# 1Sheeld_Schematics_v1_0_0.net
KiCad netlist of a schematic drawn in EAGLE
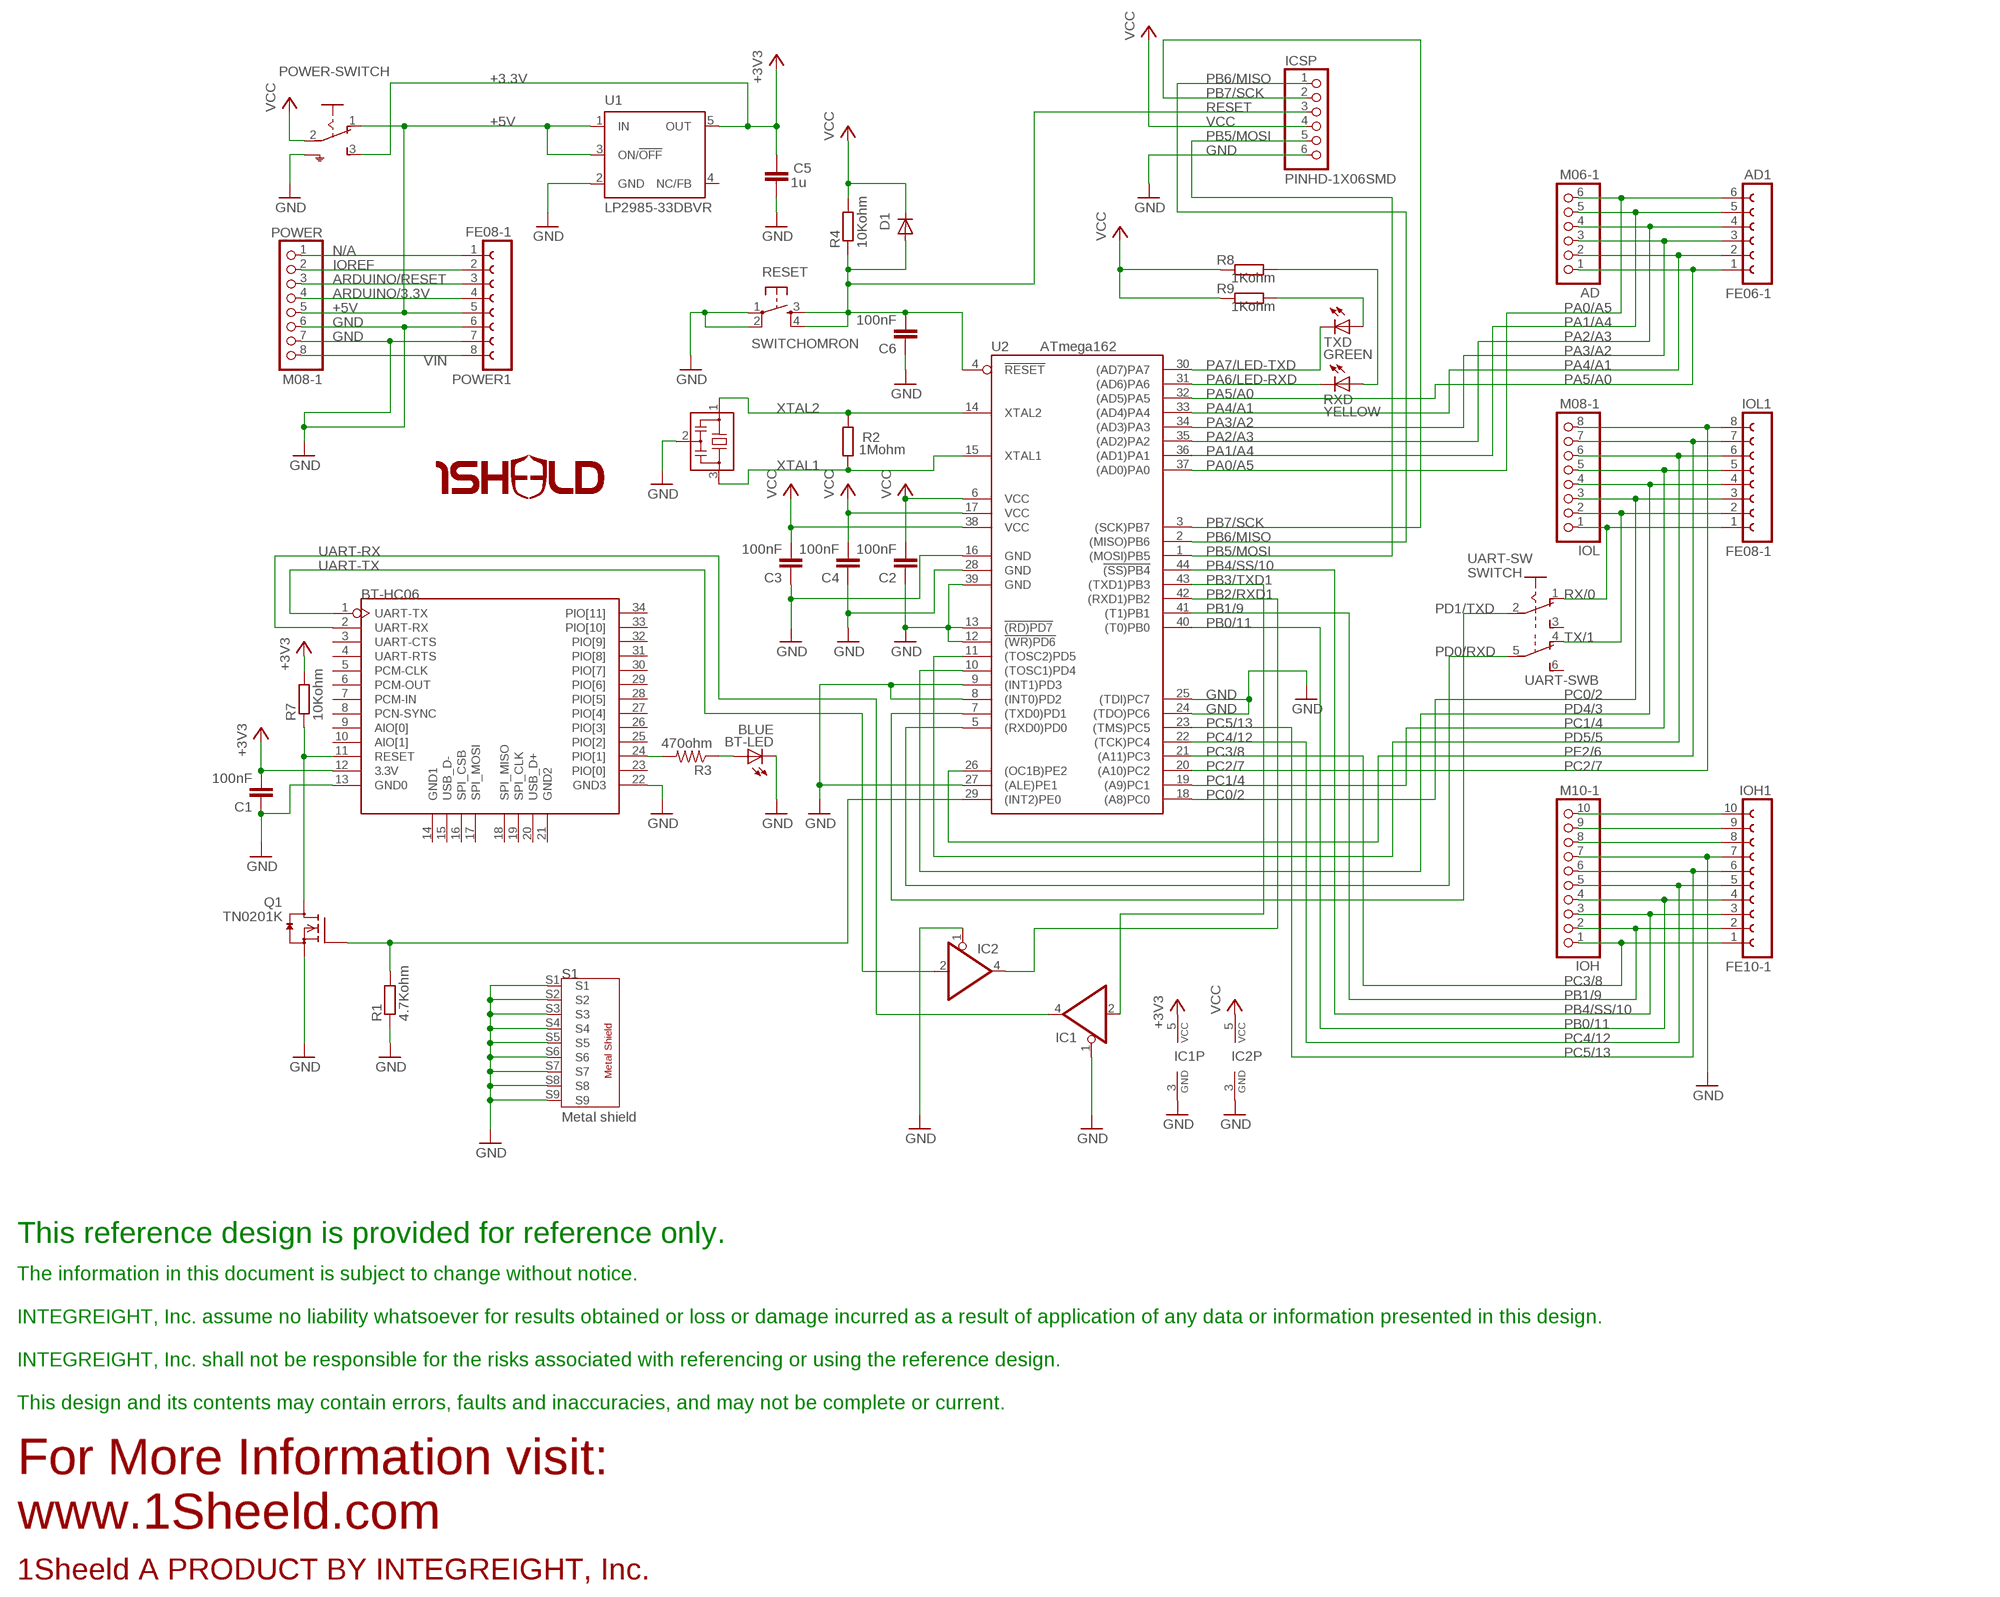
[diagram p0: schematic, sheet 1]

(export (version "E")
  (design (tool "Eeschema 10.0.6"))
  (components
    (comp (ref "AD")
      (value "M06-1")
      (footprint "eagle-import:1X06")
      (libsource (lib "eagle-import") (part "PINHD-1X6"))
    )
    (comp (ref "AD1")
      (value "FE06-1")
      (footprint "eagle-import:FE06")
      (libsource (lib "eagle-import") (part "FE06-1"))
    )
    (comp (ref "BT-HC06")
      (value "BLUETOOTH-SERIALSMD")
      (footprint "eagle-import:SERIAL_BLUETEETH")
      (libsource (lib "eagle-import") (part "BLUETOOTH-SERIALSMD"))
    )
    (comp (ref "BT-LED")
      (value "BLUE")
      (footprint "eagle-import:CHIP-LED0805")
      (libsource (lib "eagle-import") (part "LEDCHIP-LED0805"))
    )
    (comp (ref "C1")
      (value "100nF")
      (footprint "eagle-import:C0603-ROUND")
      (libsource (lib "eagle-import") (part "C-EU0603-RND"))
    )
    (comp (ref "C2")
      (value "100nF")
      (footprint "eagle-import:C0603-ROUND")
      (libsource (lib "eagle-import") (part "C-EU0603-RND"))
    )
    (comp (ref "C3")
      (value "100nF")
      (footprint "eagle-import:C0603-ROUND")
      (libsource (lib "eagle-import") (part "C-EU0603-RND"))
    )
    (comp (ref "C4")
      (value "100nF")
      (footprint "eagle-import:C0603-ROUND")
      (libsource (lib "eagle-import") (part "C-EU0603-RND"))
    )
    (comp (ref "C5")
      (value "1u")
      (footprint "eagle-import:C0603-ROUND")
      (libsource (lib "eagle-import") (part "C-EU0603-RND"))
    )
    (comp (ref "C6")
      (value "100nF")
      (footprint "eagle-import:C0603-ROUND")
      (libsource (lib "eagle-import") (part "C-EU0603-RND"))
    )
    (comp (ref "D1")
      (value "CD1206-S01575")
      (footprint "eagle-import:MINIMELF")
      (libsource (lib "eagle-import") (part "DIODE-MINIMELF"))
    )
    (comp (ref "IC1")
      (value "74LVC1G125DBV")
      (footprint "eagle-import:SOT23-5")
      (libsource (lib "eagle-import") (part "741G125DBVLVC"))
    )
    (comp (ref "IC2")
      (value "74LVC1G125DBV")
      (footprint "eagle-import:SOT23-5")
      (libsource (lib "eagle-import") (part "741G125DBVLVC"))
    )
    (comp (ref "ICSP")
      (value "PINHD-1X06SMD")
      (footprint "eagle-import:1X06_90SMD")
      (libsource (lib "eagle-import") (part "PINHD-1X06SMD"))
    )
    (comp (ref "IOH")
      (value "M10-1")
      (footprint "eagle-import:1X10")
      (libsource (lib "eagle-import") (part "PINHD-1X10_ARD"))
    )
    (comp (ref "IOH1")
      (value "FE10-1")
      (footprint "eagle-import:FE10")
      (libsource (lib "eagle-import") (part "FE10-1"))
    )
    (comp (ref "IOL")
      (value "M08-1")
      (footprint "eagle-import:1X08")
      (libsource (lib "eagle-import") (part "PINHD-1X8"))
    )
    (comp (ref "IOL1")
      (value "FE08-1")
      (footprint "eagle-import:FE08")
      (libsource (lib "eagle-import") (part "FE08-1"))
    )
    (comp (ref "POWER")
      (value "M08-1")
      (footprint "eagle-import:1X08")
      (libsource (lib "eagle-import") (part "PINHD-1X8"))
    )
    (comp (ref "POWER-SWITCH")
      (value "MULTICOMP - MSS3-V-T/R")
      (footprint "eagle-import:SWITCHMULTI")
      (fields (field (name "MANUFACTURER-PART") "MSS3-V-T/R"))
      (libsource (lib "eagle-import") (part "SWITCHMULTI"))
    )
    (comp (ref "POWER1")
      (value "FE08-1")
      (footprint "eagle-import:FE08")
      (libsource (lib "eagle-import") (part "FE08-1"))
    )
    (comp (ref "Q1")
      (value "TN0201K")
      (footprint "eagle-import:SOT23")
      (libsource (lib "eagle-import") (part "TN0201K"))
    )
    (comp (ref "R1")
      (value "4.7Kohm")
      (footprint "eagle-import:M0805")
      (libsource (lib "eagle-import") (part "rcl_R-EU_M0805"))
    )
    (comp (ref "R2")
      (value "1Mohm")
      (footprint "eagle-import:R0603-ROUND")
      (libsource (lib "eagle-import") (part "R-EU_R0603"))
    )
    (comp (ref "R3")
      (value "470ohm")
      (footprint "eagle-import:0402-RES")
      (libsource (lib "eagle-import") (part "RESISTOR0402-RES"))
    )
    (comp (ref "R4")
      (value "10Kohm")
      (footprint "eagle-import:M0805")
      (libsource (lib "eagle-import") (part "rcl_R-EU_M0805"))
    )
    (comp (ref "R7")
      (value "10Kohm")
      (footprint "eagle-import:M0805")
      (libsource (lib "eagle-import") (part "rcl_R-EU_M0805"))
    )
    (comp (ref "R8")
      (value "1Kohm")
      (footprint "eagle-import:R0603-ROUND")
      (libsource (lib "eagle-import") (part "R-EU_R0603"))
    )
    (comp (ref "R9")
      (value "1Kohm")
      (footprint "eagle-import:R0603-ROUND")
      (libsource (lib "eagle-import") (part "R-EU_R0603"))
    )
    (comp (ref "RESET")
      (value "SWITCHOMRON")
      (footprint "eagle-import:OMRONSWITCH")
      (fields (field (name "MANUFACTURER-PART") "B3SL-1022P "))
      (libsource (lib "eagle-import") (part "SWITCHOMRON"))
    )
    (comp (ref "RXD")
      (value "YELLOW")
      (footprint "eagle-import:CHIP-LED0805")
      (libsource (lib "eagle-import") (part "LEDCHIP-LED0805"))
    )
    (comp (ref "S1")
      (value "Metal shield")
      (footprint "eagle-import:BT_SHIELD")
      (libsource (lib "eagle-import") (part "EMI_SHIELD_BT"))
    )
    (comp (ref "TXD")
      (value "GREEN")
      (footprint "eagle-import:CHIP-LED0805")
      (libsource (lib "eagle-import") (part "LEDCHIP-LED0805"))
    )
    (comp (ref "U1")
      (value "LP2985-33DBVR")
      (footprint "eagle-import:SOT23-DBV")
      (libsource (lib "eagle-import") (part "LP2985-XXDBVR33"))
    )
    (comp (ref "U2")
      (value "ATmega162")
      (footprint "eagle-import:TQFP44")
      (libsource (lib "eagle-import") (part "ATMEGA162"))
    )
    (comp (ref "UART-SW")
      (value "SWITCH")
      (footprint "eagle-import:SWITCH")
      (libsource (lib "eagle-import") (part "SWITCH"))
    )
    (comp (ref "Y1")
      (value "CSTCR7M37G53-R0 7.37MHZ")
      (footprint "eagle-import:CSTCR6M")
      (libsource (lib "eagle-import") (part "CSTCR7M37G53-R0"))
    )
  )
  (nets
    (net (code "1") (name "+3V3") (class "Default")
      (node (ref "BT-HC06") (pin "12") (pinfunction "3.3V_12") (pintype "bidirectional"))
      (node (ref "C1") (pin "2") (pinfunction "2_2") (pintype "passive"))
      (node (ref "C5") (pin "2") (pinfunction "2_2") (pintype "passive"))
      (node (ref "IC1") (pin "5") (pinfunction "VCC_5") (pintype "power_in"))
      (node (ref "POWER-SWITCH") (pin "3") (pinfunction "S_3") (pintype "passive"))
      (node (ref "R7") (pin "2") (pinfunction "2_2") (pintype "passive"))
      (node (ref "U1") (pin "5") (pinfunction "OUT_5") (pintype "passive"))
    )
    (net (code "2") (name "/+5V") (class "Default")
      (node (ref "POWER") (pin "5") (pinfunction "5_5") (pintype "passive"))
      (node (ref "POWER-SWITCH") (pin "1") (pinfunction "O_1") (pintype "passive"))
      (node (ref "POWER1") (pin "5") (pinfunction "5_5") (pintype "passive"))
      (node (ref "U1") (pin "1") (pinfunction "IN_1") (pintype "input"))
      (node (ref "U1") (pin "3") (pinfunction "ON/~{OFF}_3") (pintype "input"))
    )
    (net (code "3") (name "/ARDUINO{slash}3.3V") (class "Default")
      (node (ref "POWER") (pin "4") (pinfunction "4_4") (pintype "passive"))
      (node (ref "POWER1") (pin "4") (pinfunction "4_4") (pintype "passive"))
    )
    (net (code "4") (name "/ARDUINO{slash}RESET") (class "Default")
      (node (ref "POWER") (pin "3") (pinfunction "3_3") (pintype "passive"))
      (node (ref "POWER1") (pin "3") (pinfunction "3_3") (pintype "passive"))
    )
    (net (code "5") (name "/IOREF") (class "Default")
      (node (ref "POWER") (pin "2") (pinfunction "2_2") (pintype "passive"))
      (node (ref "POWER1") (pin "2") (pinfunction "2_2") (pintype "passive"))
    )
    (net (code "6") (name "/N{slash}A") (class "Default")
      (node (ref "POWER") (pin "1") (pinfunction "1_1") (pintype "passive"))
      (node (ref "POWER1") (pin "1") (pinfunction "1_1") (pintype "passive"))
    )
    (net (code "7") (name "/PA0{slash}A5") (class "Default")
      (node (ref "AD") (pin "6") (pinfunction "6_6") (pintype "passive"))
      (node (ref "AD1") (pin "6") (pinfunction "6_6") (pintype "passive"))
      (node (ref "U2") (pin "37") (pinfunction "(AD0)PA0_37") (pintype "bidirectional"))
    )
    (net (code "8") (name "/PA1{slash}A4") (class "Default")
      (node (ref "AD") (pin "5") (pinfunction "5_5") (pintype "passive"))
      (node (ref "AD1") (pin "5") (pinfunction "5_5") (pintype "passive"))
      (node (ref "U2") (pin "36") (pinfunction "(AD1)PA1_36") (pintype "bidirectional"))
    )
    (net (code "9") (name "/PA2{slash}A3") (class "Default")
      (node (ref "AD") (pin "4") (pinfunction "4_4") (pintype "passive"))
      (node (ref "AD1") (pin "4") (pinfunction "4_4") (pintype "passive"))
      (node (ref "U2") (pin "35") (pinfunction "(AD2)PA2_35") (pintype "bidirectional"))
    )
    (net (code "10") (name "/PA3{slash}A2") (class "Default")
      (node (ref "AD") (pin "3") (pinfunction "3_3") (pintype "passive"))
      (node (ref "AD1") (pin "3") (pinfunction "3_3") (pintype "passive"))
      (node (ref "U2") (pin "34") (pinfunction "(AD3)PA3_34") (pintype "bidirectional"))
    )
    (net (code "11") (name "/PA4{slash}A1") (class "Default")
      (node (ref "AD") (pin "2") (pinfunction "2_2") (pintype "passive"))
      (node (ref "AD1") (pin "2") (pinfunction "2_2") (pintype "passive"))
      (node (ref "U2") (pin "33") (pinfunction "(AD4)PA4_33") (pintype "bidirectional"))
    )
    (net (code "12") (name "/PA5{slash}A0") (class "Default")
      (node (ref "AD") (pin "1") (pinfunction "1_1") (pintype "passive"))
      (node (ref "AD1") (pin "1") (pinfunction "1_1") (pintype "passive"))
      (node (ref "U2") (pin "32") (pinfunction "(AD5)PA5_32") (pintype "bidirectional"))
    )
    (net (code "13") (name "/PA6{slash}LED-RXD") (class "Default")
      (node (ref "RXD") (pin "C") (pinfunction "C_C") (pintype "passive"))
      (node (ref "U2") (pin "31") (pinfunction "(AD6)PA6_31") (pintype "bidirectional"))
    )
    (net (code "14") (name "/PA7{slash}LED-TXD") (class "Default")
      (node (ref "TXD") (pin "C") (pinfunction "C_C") (pintype "passive"))
      (node (ref "U2") (pin "30") (pinfunction "(AD7)PA7_30") (pintype "bidirectional"))
    )
    (net (code "15") (name "/PB0{slash}11") (class "Default")
      (node (ref "IOH") (pin "4") (pinfunction "4_4") (pintype "passive"))
      (node (ref "IOH1") (pin "4") (pinfunction "4_4") (pintype "passive"))
      (node (ref "U2") (pin "40") (pinfunction "(T0)PB0_40") (pintype "bidirectional"))
    )
    (net (code "16") (name "/PB1{slash}9") (class "Default")
      (node (ref "IOH") (pin "2") (pinfunction "2_2") (pintype "passive"))
      (node (ref "IOH1") (pin "2") (pinfunction "2_2") (pintype "passive"))
      (node (ref "U2") (pin "41") (pinfunction "(T1)PB1_41") (pintype "bidirectional"))
    )
    (net (code "17") (name "/PB2{slash}RXD1") (class "Default")
      (node (ref "IC2") (pin "4") (pinfunction "O_4") (pintype "tri_state"))
      (node (ref "U2") (pin "42") (pinfunction "(RXD1)PB2_42") (pintype "bidirectional"))
    )
    (net (code "18") (name "/PB3{slash}TXD1") (class "Default")
      (node (ref "IC1") (pin "2") (pinfunction "I_2") (pintype "input"))
      (node (ref "U2") (pin "43") (pinfunction "(TXD1)PB3_43") (pintype "bidirectional"))
    )
    (net (code "19") (name "/PB4{slash}SS{slash}10") (class "Default")
      (node (ref "IOH") (pin "3") (pinfunction "3_3") (pintype "passive"))
      (node (ref "IOH1") (pin "3") (pinfunction "3_3") (pintype "passive"))
      (node (ref "U2") (pin "44") (pinfunction "~{(SS})PB4_44") (pintype "bidirectional"))
    )
    (net (code "20") (name "/PB5{slash}MOSI") (class "Default")
      (node (ref "ICSP") (pin "5") (pinfunction "5_5") (pintype "passive"))
      (node (ref "U2") (pin "1") (pinfunction "(MOSI)PB5_1") (pintype "bidirectional"))
    )
    (net (code "21") (name "/PB6{slash}MISO") (class "Default")
      (node (ref "ICSP") (pin "1") (pinfunction "1_1") (pintype "passive"))
      (node (ref "U2") (pin "2") (pinfunction "(MISO)PB6_2") (pintype "bidirectional"))
    )
    (net (code "22") (name "/PB7{slash}SCK") (class "Default")
      (node (ref "ICSP") (pin "2") (pinfunction "2_2") (pintype "passive"))
      (node (ref "U2") (pin "3") (pinfunction "(SCK)PB7_3") (pintype "bidirectional"))
    )
    (net (code "23") (name "/PC0{slash}2") (class "Default")
      (node (ref "IOL") (pin "3") (pinfunction "3_3") (pintype "passive"))
      (node (ref "IOL1") (pin "3") (pinfunction "3_3") (pintype "passive"))
      (node (ref "U2") (pin "18") (pinfunction "(A8)PC0_18") (pintype "bidirectional"))
    )
    (net (code "24") (name "/PC1{slash}4") (class "Default")
      (node (ref "IOL") (pin "5") (pinfunction "5_5") (pintype "passive"))
      (node (ref "IOL1") (pin "5") (pinfunction "5_5") (pintype "passive"))
      (node (ref "U2") (pin "19") (pinfunction "(A9)PC1_19") (pintype "bidirectional"))
    )
    (net (code "25") (name "/PC2{slash}7") (class "Default")
      (node (ref "IOL") (pin "8") (pinfunction "8_8") (pintype "passive"))
      (node (ref "IOL1") (pin "8") (pinfunction "8_8") (pintype "passive"))
      (node (ref "U2") (pin "20") (pinfunction "(A10)PC2_20") (pintype "bidirectional"))
    )
    (net (code "26") (name "/PC3{slash}8") (class "Default")
      (node (ref "IOH") (pin "1") (pinfunction "1_1") (pintype "passive"))
      (node (ref "IOH1") (pin "1") (pinfunction "1_1") (pintype "passive"))
      (node (ref "U2") (pin "21") (pinfunction "(A11)PC3_21") (pintype "bidirectional"))
    )
    (net (code "27") (name "/PC4{slash}12") (class "Default")
      (node (ref "IOH") (pin "5") (pinfunction "5_5") (pintype "passive"))
      (node (ref "IOH1") (pin "5") (pinfunction "5_5") (pintype "passive"))
      (node (ref "U2") (pin "22") (pinfunction "(TCK)PC4_22") (pintype "bidirectional"))
    )
    (net (code "28") (name "/PC5{slash}13") (class "Default")
      (node (ref "IOH") (pin "6") (pinfunction "6_6") (pintype "passive"))
      (node (ref "IOH1") (pin "6") (pinfunction "6_6") (pintype "passive"))
      (node (ref "U2") (pin "23") (pinfunction "(TMS)PC5_23") (pintype "bidirectional"))
    )
    (net (code "29") (name "/PD0{slash}RXD") (class "Default")
      (node (ref "U2") (pin "5") (pinfunction "(RXD0)PD0_5") (pintype "bidirectional"))
      (node (ref "UART-SW") (pin "5") (pinfunction "P_5") (pintype "passive"))
    )
    (net (code "30") (name "/PD1{slash}TXD") (class "Default")
      (node (ref "U2") (pin "7") (pinfunction "(TXD0)PD1_7") (pintype "bidirectional"))
      (node (ref "UART-SW") (pin "2") (pinfunction "P_2") (pintype "passive"))
    )
    (net (code "31") (name "/PD4{slash}3") (class "Default")
      (node (ref "IOL") (pin "4") (pinfunction "4_4") (pintype "passive"))
      (node (ref "IOL1") (pin "4") (pinfunction "4_4") (pintype "passive"))
      (node (ref "U2") (pin "10") (pinfunction "(TOSC1)PD4_10") (pintype "bidirectional"))
    )
    (net (code "32") (name "/PD5{slash}5") (class "Default")
      (node (ref "IOL") (pin "6") (pinfunction "6_6") (pintype "passive"))
      (node (ref "IOL1") (pin "6") (pinfunction "6_6") (pintype "passive"))
      (node (ref "U2") (pin "11") (pinfunction "(TOSC2)PD5_11") (pintype "bidirectional"))
    )
    (net (code "33") (name "/PE2{slash}6") (class "Default")
      (node (ref "IOL") (pin "7") (pinfunction "7_7") (pintype "passive"))
      (node (ref "IOL1") (pin "7") (pinfunction "7_7") (pintype "passive"))
      (node (ref "U2") (pin "26") (pinfunction "(OC1B)PE2_26") (pintype "bidirectional"))
    )
    (net (code "34") (name "/RESET") (class "Default")
      (node (ref "C6") (pin "2") (pinfunction "2_2") (pintype "passive"))
      (node (ref "D1") (pin "A") (pinfunction "A_A") (pintype "passive"))
      (node (ref "ICSP") (pin "3") (pinfunction "3_3") (pintype "passive"))
      (node (ref "R4") (pin "1") (pinfunction "1_1") (pintype "passive"))
      (node (ref "RESET") (pin "3") (pinfunction "S_3") (pintype "passive"))
      (node (ref "RESET") (pin "4") (pinfunction "S1_4") (pintype "passive"))
      (node (ref "U2") (pin "4") (pinfunction "~{RESET}_4") (pintype "input"))
    )
    (net (code "35") (name "/RX{slash}0") (class "Default")
      (node (ref "IOL") (pin "1") (pinfunction "1_1") (pintype "passive"))
      (node (ref "IOL1") (pin "1") (pinfunction "1_1") (pintype "passive"))
      (node (ref "UART-SW") (pin "1") (pinfunction "O_1") (pintype "passive"))
    )
    (net (code "36") (name "/TX{slash}1") (class "Default")
      (node (ref "IOL") (pin "2") (pinfunction "2_2") (pintype "passive"))
      (node (ref "IOL1") (pin "2") (pinfunction "2_2") (pintype "passive"))
      (node (ref "UART-SW") (pin "4") (pinfunction "O_4") (pintype "passive"))
    )
    (net (code "37") (name "/UART-RX") (class "Default")
      (node (ref "BT-HC06") (pin "2") (pinfunction "UART-RX_2") (pintype "bidirectional"))
      (node (ref "IC1") (pin "4") (pinfunction "O_4") (pintype "tri_state"))
    )
    (net (code "38") (name "/UART-TX") (class "Default")
      (node (ref "BT-HC06") (pin "1") (pinfunction "UART-TX_1") (pintype "bidirectional"))
      (node (ref "IC2") (pin "2") (pinfunction "I_2") (pintype "input"))
    )
    (net (code "39") (name "/VIN") (class "Default")
      (node (ref "POWER") (pin "8") (pinfunction "8_8") (pintype "passive"))
      (node (ref "POWER1") (pin "8") (pinfunction "8_8") (pintype "passive"))
    )
    (net (code "40") (name "/XTAL1") (class "Default")
      (node (ref "R2") (pin "1") (pinfunction "1_1") (pintype "passive"))
      (node (ref "U2") (pin "15") (pinfunction "XTAL1_15") (pintype "input"))
      (node (ref "Y1") (pin "3") (pinfunction "3_3") (pintype "passive"))
    )
    (net (code "41") (name "/XTAL2") (class "Default")
      (node (ref "R2") (pin "2") (pinfunction "2_2") (pintype "passive"))
      (node (ref "U2") (pin "14") (pinfunction "XTAL2_14") (pintype "input"))
      (node (ref "Y1") (pin "1") (pinfunction "1_1") (pintype "passive"))
    )
    (net (code "42") (name "GND") (class "Default")
      (node (ref "BT-HC06") (pin "13") (pinfunction "GND0_13") (pintype "bidirectional"))
      (node (ref "BT-HC06") (pin "22") (pinfunction "GND3_22") (pintype "bidirectional"))
      (node (ref "BT-LED") (pin "C") (pinfunction "C_C") (pintype "passive"))
      (node (ref "C1") (pin "1") (pinfunction "1_1") (pintype "passive"))
      (node (ref "C2") (pin "1") (pinfunction "1_1") (pintype "passive"))
      (node (ref "C3") (pin "1") (pinfunction "1_1") (pintype "passive"))
      (node (ref "C4") (pin "1") (pinfunction "1_1") (pintype "passive"))
      (node (ref "C5") (pin "1") (pinfunction "1_1") (pintype "passive"))
      (node (ref "C6") (pin "1") (pinfunction "1_1") (pintype "passive"))
      (node (ref "IC1") (pin "1") (pinfunction "OE_1") (pintype "input"))
      (node (ref "IC1") (pin "3") (pinfunction "GND_3") (pintype "power_in"))
      (node (ref "IC2") (pin "1") (pinfunction "OE_1") (pintype "input"))
      (node (ref "IC2") (pin "3") (pinfunction "GND_3") (pintype "power_in"))
      (node (ref "ICSP") (pin "6") (pinfunction "6_6") (pintype "passive"))
      (node (ref "IOH") (pin "7") (pinfunction "7_7") (pintype "passive"))
      (node (ref "IOH1") (pin "7") (pinfunction "7_7") (pintype "passive"))
      (node (ref "POWER") (pin "6") (pinfunction "6_6") (pintype "passive"))
      (node (ref "POWER") (pin "7") (pinfunction "7_7") (pintype "passive"))
      (node (ref "POWER-SWITCH") (pin "P$4") (pinfunction "SH_P$4") (pintype "passive"))
      (node (ref "POWER-SWITCH") (pin "P$5") (pinfunction "SH_P$5") (pintype "passive"))
      (node (ref "POWER-SWITCH") (pin "P$6") (pinfunction "SH_P$6") (pintype "passive"))
      (node (ref "POWER-SWITCH") (pin "P$7") (pinfunction "SH_P$7") (pintype "passive"))
      (node (ref "POWER1") (pin "6") (pinfunction "6_6") (pintype "passive"))
      (node (ref "POWER1") (pin "7") (pinfunction "7_7") (pintype "passive"))
      (node (ref "Q1") (pin "2") (pinfunction "S_2") (pintype "passive"))
      (node (ref "R1") (pin "1") (pinfunction "1_1") (pintype "passive"))
      (node (ref "RESET") (pin "1") (pinfunction "P_1") (pintype "passive"))
      (node (ref "RESET") (pin "2") (pinfunction "P1_2") (pintype "passive"))
      (node (ref "S1") (pin "S1") (pinfunction "S1_S1") (pintype "bidirectional"))
      (node (ref "S1") (pin "S2") (pinfunction "S2_S2") (pintype "bidirectional"))
      (node (ref "S1") (pin "S3") (pinfunction "S3_S3") (pintype "bidirectional"))
      (node (ref "S1") (pin "S4") (pinfunction "S4_S4") (pintype "bidirectional"))
      (node (ref "S1") (pin "S5") (pinfunction "S5_S5") (pintype "bidirectional"))
      (node (ref "S1") (pin "S6") (pinfunction "S6_S6") (pintype "bidirectional"))
      (node (ref "S1") (pin "S7") (pinfunction "S7_S7") (pintype "bidirectional"))
      (node (ref "S1") (pin "S8") (pinfunction "S8_S8") (pintype "bidirectional"))
      (node (ref "S1") (pin "S9") (pinfunction "S9_S9") (pintype "bidirectional"))
      (node (ref "U1") (pin "2") (pinfunction "GND_2") (pintype "power_in"))
      (node (ref "U2") (pin "12") (pinfunction "~{(WR})PD6_12") (pintype "bidirectional"))
      (node (ref "U2") (pin "13") (pinfunction "~{(RD})PD7_13") (pintype "bidirectional"))
      (node (ref "U2") (pin "16") (pinfunction "GND_16") (pintype "power_in"))
      (node (ref "U2") (pin "24") (pinfunction "(TDO)PC6_24") (pintype "bidirectional"))
      (node (ref "U2") (pin "25") (pinfunction "(TDI)PC7_25") (pintype "bidirectional"))
      (node (ref "U2") (pin "27") (pinfunction "(ALE)PE1_27") (pintype "bidirectional"))
      (node (ref "U2") (pin "28") (pinfunction "GND_28") (pintype "power_in"))
      (node (ref "U2") (pin "39") (pinfunction "GND_39") (pintype "power_in"))
      (node (ref "U2") (pin "8") (pinfunction "(INT0)PD2_8") (pintype "bidirectional"))
      (node (ref "U2") (pin "9") (pinfunction "(INT1)PD3_9") (pintype "bidirectional"))
      (node (ref "Y1") (pin "2") (pinfunction "2_2") (pintype "passive"))
    )
    (net (code "43") (name "Net-(BT-HC06-PIO[1])") (class "Default")
      (node (ref "BT-HC06") (pin "24") (pinfunction "PIO[1]_24") (pintype "bidirectional"))
      (node (ref "R3") (pin "2") (pinfunction "2_2") (pintype "passive"))
    )
    (net (code "44") (name "Net-(BT-HC06-RESET)") (class "Default")
      (node (ref "BT-HC06") (pin "11") (pinfunction "RESET_11") (pintype "bidirectional"))
      (node (ref "Q1") (pin "3") (pinfunction "D_3") (pintype "passive"))
      (node (ref "R7") (pin "1") (pinfunction "1_1") (pintype "passive"))
    )
    (net (code "45") (name "Net-(BT-LED-PadA)") (class "Default")
      (node (ref "BT-LED") (pin "A") (pinfunction "A_A") (pintype "passive"))
      (node (ref "R3") (pin "1") (pinfunction "1_1") (pintype "passive"))
    )
    (net (code "46") (name "Net-(IOH-Pad8)") (class "Default")
      (node (ref "IOH") (pin "8") (pinfunction "8_8") (pintype "passive"))
      (node (ref "IOH1") (pin "8") (pinfunction "8_8") (pintype "passive"))
    )
    (net (code "47") (name "Net-(IOH-Pad9)") (class "Default")
      (node (ref "IOH") (pin "9") (pinfunction "9_9") (pintype "passive"))
      (node (ref "IOH1") (pin "9") (pinfunction "9_9") (pintype "passive"))
    )
    (net (code "48") (name "Net-(IOH-Pad10)") (class "Default")
      (node (ref "IOH") (pin "10") (pinfunction "10_10") (pintype "passive"))
      (node (ref "IOH1") (pin "10") (pinfunction "10_10") (pintype "passive"))
    )
    (net (code "49") (name "Net-(Q1-G)") (class "Default")
      (node (ref "Q1") (pin "1") (pinfunction "G_1") (pintype "passive"))
      (node (ref "R1") (pin "2") (pinfunction "2_2") (pintype "passive"))
      (node (ref "U2") (pin "29") (pinfunction "(INT2)PE0_29") (pintype "bidirectional"))
    )
    (net (code "50") (name "Net-(R8-Pad1)") (class "Default")
      (node (ref "R8") (pin "1") (pinfunction "1_1") (pintype "passive"))
      (node (ref "RXD") (pin "A") (pinfunction "A_A") (pintype "passive"))
    )
    (net (code "51") (name "Net-(R9-Pad1)") (class "Default")
      (node (ref "R9") (pin "1") (pinfunction "1_1") (pintype "passive"))
      (node (ref "TXD") (pin "A") (pinfunction "A_A") (pintype "passive"))
    )
    (net (code "52") (name "VCC") (class "Default")
      (node (ref "C2") (pin "2") (pinfunction "2_2") (pintype "passive"))
      (node (ref "C3") (pin "2") (pinfunction "2_2") (pintype "passive"))
      (node (ref "C4") (pin "2") (pinfunction "2_2") (pintype "passive"))
      (node (ref "D1") (pin "C") (pinfunction "C_C") (pintype "passive"))
      (node (ref "IC2") (pin "5") (pinfunction "VCC_5") (pintype "power_in"))
      (node (ref "ICSP") (pin "4") (pinfunction "4_4") (pintype "passive"))
      (node (ref "POWER-SWITCH") (pin "2") (pinfunction "P_2") (pintype "passive"))
      (node (ref "R4") (pin "2") (pinfunction "2_2") (pintype "passive"))
      (node (ref "R8") (pin "2") (pinfunction "2_2") (pintype "passive"))
      (node (ref "R9") (pin "2") (pinfunction "2_2") (pintype "passive"))
      (node (ref "U2") (pin "17") (pinfunction "VCC_17") (pintype "power_in"))
      (node (ref "U2") (pin "38") (pinfunction "VCC_38") (pintype "power_in"))
      (node (ref "U2") (pin "6") (pinfunction "VCC_6") (pintype "power_in"))
    )
    (net (code "53") (name "unconnected-(BT-HC06-AIO[0]-Pad9)") (class "Default")
      (node (ref "BT-HC06") (pin "9") (pinfunction "AIO[0]_9") (pintype "bidirectional"))
    )
    (net (code "54") (name "unconnected-(BT-HC06-AIO[1]-Pad10)") (class "Default")
      (node (ref "BT-HC06") (pin "10") (pinfunction "AIO[1]_10") (pintype "bidirectional"))
    )
    (net (code "55") (name "unconnected-(BT-HC06-GND1-Pad14)") (class "Default")
      (node (ref "BT-HC06") (pin "14") (pinfunction "GND1_14") (pintype "bidirectional"))
    )
    (net (code "56") (name "unconnected-(BT-HC06-GND2-Pad21)") (class "Default")
      (node (ref "BT-HC06") (pin "21") (pinfunction "GND2_21") (pintype "bidirectional"))
    )
    (net (code "57") (name "unconnected-(BT-HC06-PCM-CLK-Pad5)") (class "Default")
      (node (ref "BT-HC06") (pin "5") (pinfunction "PCM-CLK_5") (pintype "bidirectional"))
    )
    (net (code "58") (name "unconnected-(BT-HC06-PCM-IN-Pad7)") (class "Default")
      (node (ref "BT-HC06") (pin "7") (pinfunction "PCM-IN_7") (pintype "bidirectional"))
    )
    (net (code "59") (name "unconnected-(BT-HC06-PCM-OUT-Pad6)") (class "Default")
      (node (ref "BT-HC06") (pin "6") (pinfunction "PCM-OUT_6") (pintype "bidirectional"))
    )
    (net (code "60") (name "unconnected-(BT-HC06-PCN-SYNC-Pad8)") (class "Default")
      (node (ref "BT-HC06") (pin "8") (pinfunction "PCN-SYNC_8") (pintype "bidirectional"))
    )
    (net (code "61") (name "unconnected-(BT-HC06-PIO[0]-Pad23)") (class "Default")
      (node (ref "BT-HC06") (pin "23") (pinfunction "PIO[0]_23") (pintype "bidirectional"))
    )
    (net (code "62") (name "unconnected-(BT-HC06-PIO[2]-Pad25)") (class "Default")
      (node (ref "BT-HC06") (pin "25") (pinfunction "PIO[2]_25") (pintype "bidirectional"))
    )
    (net (code "63") (name "unconnected-(BT-HC06-PIO[3]-Pad26)") (class "Default")
      (node (ref "BT-HC06") (pin "26") (pinfunction "PIO[3]_26") (pintype "bidirectional"))
    )
    (net (code "64") (name "unconnected-(BT-HC06-PIO[4]-Pad27)") (class "Default")
      (node (ref "BT-HC06") (pin "27") (pinfunction "PIO[4]_27") (pintype "bidirectional"))
    )
    (net (code "65") (name "unconnected-(BT-HC06-PIO[5]-Pad28)") (class "Default")
      (node (ref "BT-HC06") (pin "28") (pinfunction "PIO[5]_28") (pintype "bidirectional"))
    )
    (net (code "66") (name "unconnected-(BT-HC06-PIO[6]-Pad29)") (class "Default")
      (node (ref "BT-HC06") (pin "29") (pinfunction "PIO[6]_29") (pintype "bidirectional"))
    )
    (net (code "67") (name "unconnected-(BT-HC06-PIO[7]-Pad30)") (class "Default")
      (node (ref "BT-HC06") (pin "30") (pinfunction "PIO[7]_30") (pintype "bidirectional"))
    )
    (net (code "68") (name "unconnected-(BT-HC06-PIO[8]-Pad31)") (class "Default")
      (node (ref "BT-HC06") (pin "31") (pinfunction "PIO[8]_31") (pintype "bidirectional"))
    )
    (net (code "69") (name "unconnected-(BT-HC06-PIO[9]-Pad32)") (class "Default")
      (node (ref "BT-HC06") (pin "32") (pinfunction "PIO[9]_32") (pintype "bidirectional"))
    )
    (net (code "70") (name "unconnected-(BT-HC06-PIO[10]-Pad33)") (class "Default")
      (node (ref "BT-HC06") (pin "33") (pinfunction "PIO[10]_33") (pintype "bidirectional"))
    )
    (net (code "71") (name "unconnected-(BT-HC06-PIO[11]-Pad34)") (class "Default")
      (node (ref "BT-HC06") (pin "34") (pinfunction "PIO[11]_34") (pintype "bidirectional"))
    )
    (net (code "72") (name "unconnected-(BT-HC06-SPI_CLK-Pad19)") (class "Default")
      (node (ref "BT-HC06") (pin "19") (pinfunction "SPI_CLK_19") (pintype "bidirectional"))
    )
    (net (code "73") (name "unconnected-(BT-HC06-SPI_CSB-Pad16)") (class "Default")
      (node (ref "BT-HC06") (pin "16") (pinfunction "SPI_CSB_16") (pintype "bidirectional"))
    )
    (net (code "74") (name "unconnected-(BT-HC06-SPI_MISO-Pad18)") (class "Default")
      (node (ref "BT-HC06") (pin "18") (pinfunction "SPI_MISO_18") (pintype "bidirectional"))
    )
    (net (code "75") (name "unconnected-(BT-HC06-SPI_MOSI-Pad17)") (class "Default")
      (node (ref "BT-HC06") (pin "17") (pinfunction "SPI_MOSI_17") (pintype "bidirectional"))
    )
    (net (code "76") (name "unconnected-(BT-HC06-UART-CTS-Pad3)") (class "Default")
      (node (ref "BT-HC06") (pin "3") (pinfunction "UART-CTS_3") (pintype "bidirectional"))
    )
    (net (code "77") (name "unconnected-(BT-HC06-UART-RTS-Pad4)") (class "Default")
      (node (ref "BT-HC06") (pin "4") (pinfunction "UART-RTS_4") (pintype "bidirectional"))
    )
    (net (code "78") (name "unconnected-(BT-HC06-USB_D+-Pad20)") (class "Default")
      (node (ref "BT-HC06") (pin "20") (pinfunction "USB_D+_20") (pintype "bidirectional"))
    )
    (net (code "79") (name "unconnected-(BT-HC06-USB_D--Pad15)") (class "Default")
      (node (ref "BT-HC06") (pin "15") (pinfunction "USB_D-_15") (pintype "bidirectional"))
    )
    (net (code "80") (name "unconnected-(U1-NC{slash}FB-Pad4)") (class "Default")
      (node (ref "U1") (pin "4") (pinfunction "NC/FB_4") (pintype "passive"))
    )
    (net (code "81") (name "unconnected-(UART-SWA-S-Pad3)") (class "Default")
      (node (ref "UART-SW") (pin "3") (pinfunction "S_3") (pintype "passive"))
    )
    (net (code "82") (name "unconnected-(UART-SWB-S-Pad6)") (class "Default")
      (node (ref "UART-SW") (pin "6") (pinfunction "S_6") (pintype "passive"))
    )
  )
)
